# wrist_watch_v1.net
KiCad netlist of a schematic drawn in EAGLE
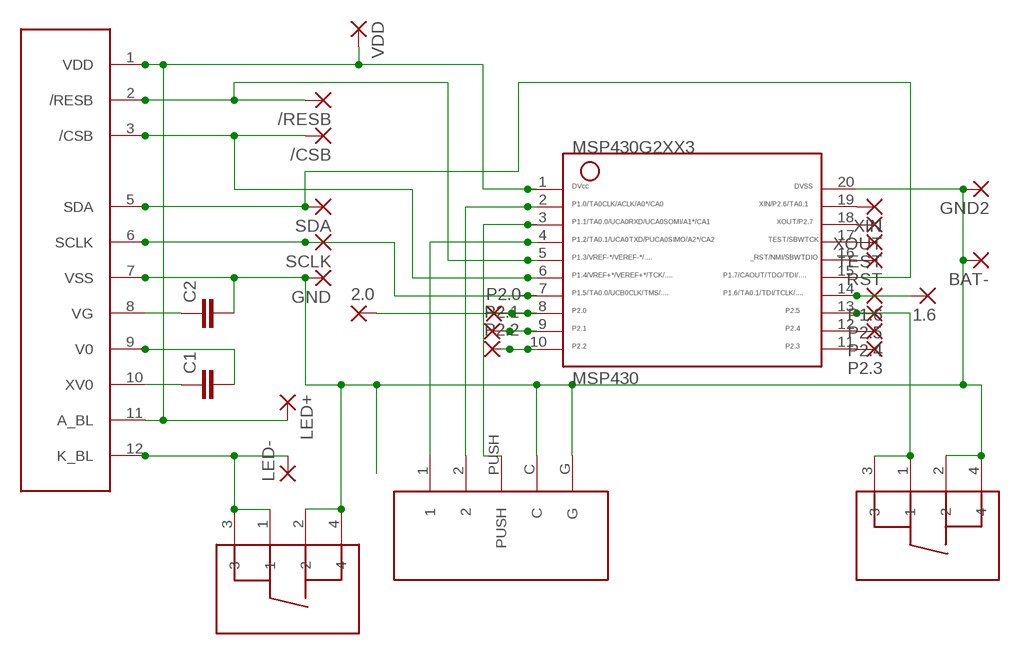
[diagram p0: schematic, sheet 1]

(export (version "E")
  (design (tool "Eeschema 10.0.6"))
  (components
    (comp (ref "/CSB")
      (value "1,6/0,9")
      (footprint "eagle-import:1,6_0,9")
      (libsource (lib "eagle-import") (part "1,6/0,9"))
    )
    (comp (ref "/RESB")
      (value "1,6/0,9")
      (footprint "eagle-import:1,6_0,9")
      (libsource (lib "eagle-import") (part "1,6/0,9"))
    )
    (comp (ref "1.6")
      (value "1,6/0,9")
      (footprint "eagle-import:1,6_0,9")
      (libsource (lib "eagle-import") (part "1,6/0,9"))
    )
    (comp (ref "2.0")
      (value "1,6/0,9")
      (footprint "eagle-import:1,6_0,9")
      (libsource (lib "eagle-import") (part "1,6/0,9"))
    )
    (comp (ref "BAT-")
      (value "SMD5")
      (footprint "eagle-import:SMD2,54-5,08")
      (libsource (lib "eagle-import") (part "SMD5"))
    )
    (comp (ref "C1")
      (value "CAP0805")
      (footprint "eagle-import:0805")
      (libsource (lib "eagle-import") (part "CAP0805"))
    )
    (comp (ref "C2")
      (value "CAP0805")
      (footprint "eagle-import:0805")
      (libsource (lib "eagle-import") (part "CAP0805"))
    )
    (comp (ref "GND")
      (value "1,6/0,9")
      (footprint "eagle-import:1,6_0,9")
      (libsource (lib "eagle-import") (part "1,6/0,9"))
    )
    (comp (ref "GND2")
      (value "SMD2")
      (footprint "eagle-import:SMD1,27-2,54")
      (libsource (lib "eagle-import") (part "SMD2"))
    )
    (comp (ref "LED+")
      (value "1,6/0,9")
      (footprint "eagle-import:1,6_0,9")
      (libsource (lib "eagle-import") (part "1,6/0,9"))
    )
    (comp (ref "LED-")
      (value "1,6/0,9")
      (footprint "eagle-import:1,6_0,9")
      (libsource (lib "eagle-import") (part "1,6/0,9"))
    )
    (comp (ref "MSP430")
      (value "G2XX3---PW20")
      (footprint "eagle-import:PW20")
      (libsource (lib "eagle-import") (part "G2XX3---PW20"))
    )
    (comp (ref "P1.6")
      (value "SMD2")
      (footprint "eagle-import:SMD1,27-2,54")
      (libsource (lib "eagle-import") (part "SMD2"))
    )
    (comp (ref "P2.0")
      (value "SMD2")
      (footprint "eagle-import:SMD1,27-2,54")
      (libsource (lib "eagle-import") (part "SMD2"))
    )
    (comp (ref "P2.1")
      (value "SMD2")
      (footprint "eagle-import:SMD1,27-2,54")
      (libsource (lib "eagle-import") (part "SMD2"))
    )
    (comp (ref "P2.2")
      (value "SMD2")
      (footprint "eagle-import:SMD1,27-2,54")
      (libsource (lib "eagle-import") (part "SMD2"))
    )
    (comp (ref "P2.3")
      (value "SMD2")
      (footprint "eagle-import:SMD1,27-2,54")
      (libsource (lib "eagle-import") (part "SMD2"))
    )
    (comp (ref "P2.4")
      (value "SMD2")
      (footprint "eagle-import:SMD1,27-2,54")
      (libsource (lib "eagle-import") (part "SMD2"))
    )
    (comp (ref "P2.5")
      (value "SMD2")
      (footprint "eagle-import:SMD1,27-2,54")
      (libsource (lib "eagle-import") (part "SMD2"))
    )
    (comp (ref "RST")
      (value "1,6/0,9")
      (footprint "eagle-import:1,6_0,9")
      (libsource (lib "eagle-import") (part "1,6/0,9"))
    )
    (comp (ref "SCLK")
      (value "1,6/0,9")
      (footprint "eagle-import:1,6_0,9")
      (libsource (lib "eagle-import") (part "1,6/0,9"))
    )
    (comp (ref "SDA")
      (value "1,6/0,9")
      (footprint "eagle-import:1,6_0,9")
      (libsource (lib "eagle-import") (part "1,6/0,9"))
    )
    (comp (ref "TEST")
      (value "1,6/0,9")
      (footprint "eagle-import:1,6_0,9")
      (libsource (lib "eagle-import") (part "1,6/0,9"))
    )
    (comp (ref "U$1")
      (value "PE9665WRFPE9665WRF-WHOLE")
      (footprint "eagle-import:PE9665WRF")
      (libsource (lib "eagle-import") (part "PE9665WRFPE9665WRF-WHOLE"))
    )
    (comp (ref "U$2")
      (value "MCPTCF-V")
      (footprint "eagle-import:MCPTCF-V")
      (libsource (lib "eagle-import") (part "MCPTCF-V"))
    )
    (comp (ref "U$3")
      (value "MCPL3-BC-V")
      (footprint "eagle-import:MCPL3-BC-V")
      (libsource (lib "eagle-import") (part "MCPL3-BC-V"))
    )
    (comp (ref "U$4")
      (value "MCPTCF-V")
      (footprint "eagle-import:MCPTCF-V")
      (libsource (lib "eagle-import") (part "MCPTCF-V"))
    )
    (comp (ref "VDD")
      (value "1,6/0,9")
      (footprint "eagle-import:1,6_0,9")
      (libsource (lib "eagle-import") (part "1,6/0,9"))
    )
    (comp (ref "XIN")
      (value "SMD2")
      (footprint "eagle-import:SMD1,27-2,54")
      (libsource (lib "eagle-import") (part "SMD2"))
    )
    (comp (ref "XOUT")
      (value "SMD2")
      (footprint "eagle-import:SMD1,27-2,54")
      (libsource (lib "eagle-import") (part "SMD2"))
    )
  )
  (nets
    (net (code "1") (name "Net-(/CSB-P)") (class "Default")
      (node (ref "/CSB") (pin "1") (pinfunction "P_1") (pintype "passive"))
      (node (ref "MSP430") (pin "6") (pinfunction "6_6") (pintype "bidirectional"))
      (node (ref "U$1") (pin "3") (pinfunction "/CSB_3") (pintype "bidirectional"))
    )
    (net (code "2") (name "Net-(/RESB-P)") (class "Default")
      (node (ref "/RESB") (pin "1") (pinfunction "P_1") (pintype "passive"))
      (node (ref "MSP430") (pin "5") (pinfunction "5_5") (pintype "bidirectional"))
      (node (ref "U$1") (pin "2") (pinfunction "/RESB_2") (pintype "bidirectional"))
    )
    (net (code "3") (name "Net-(1.6-P)") (class "Default")
      (node (ref "1.6") (pin "1") (pinfunction "P_1") (pintype "passive"))
      (node (ref "MSP430") (pin "14") (pinfunction "14_14") (pintype "bidirectional"))
      (node (ref "P1.6") (pin "1") (pinfunction "P_1") (pintype "passive"))
    )
    (net (code "4") (name "Net-(2.0-P)") (class "Default")
      (node (ref "2.0") (pin "1") (pinfunction "P_1") (pintype "passive"))
      (node (ref "MSP430") (pin "8") (pinfunction "8_8") (pintype "bidirectional"))
      (node (ref "P2.0") (pin "1") (pinfunction "P_1") (pintype "passive"))
    )
    (net (code "5") (name "Net-(BAT--P)") (class "Default")
      (node (ref "BAT-") (pin "1") (pinfunction "P_1") (pintype "passive"))
      (node (ref "C2") (pin "2") (pinfunction "2_2") (pintype "passive"))
      (node (ref "GND") (pin "1") (pinfunction "P_1") (pintype "passive"))
      (node (ref "GND2") (pin "1") (pinfunction "P_1") (pintype "passive"))
      (node (ref "MSP430") (pin "20") (pinfunction "20_20") (pintype "bidirectional"))
      (node (ref "U$1") (pin "7") (pinfunction "VSS_7") (pintype "bidirectional"))
      (node (ref "U$2") (pin "2") (pinfunction "2_2") (pintype "bidirectional"))
      (node (ref "U$2") (pin "4") (pinfunction "4_4") (pintype "bidirectional"))
      (node (ref "U$3") (pin "C") (pinfunction "C_C") (pintype "bidirectional"))
      (node (ref "U$3") (pin "G") (pinfunction "G_G") (pintype "bidirectional"))
      (node (ref "U$4") (pin "2") (pinfunction "2_2") (pintype "bidirectional"))
      (node (ref "U$4") (pin "4") (pinfunction "4_4") (pintype "bidirectional"))
    )
    (net (code "6") (name "Net-(LED+-P)") (class "Default")
      (node (ref "LED+") (pin "1") (pinfunction "P_1") (pintype "passive"))
      (node (ref "MSP430") (pin "1") (pinfunction "1_1") (pintype "bidirectional"))
      (node (ref "U$1") (pin "1") (pinfunction "VDD_1") (pintype "bidirectional"))
      (node (ref "U$1") (pin "11") (pinfunction "A_BL_11") (pintype "bidirectional"))
      (node (ref "VDD") (pin "1") (pinfunction "P_1") (pintype "passive"))
    )
    (net (code "7") (name "Net-(LED--P)") (class "Default")
      (node (ref "LED-") (pin "1") (pinfunction "P_1") (pintype "passive"))
      (node (ref "U$1") (pin "12") (pinfunction "K_BL_12") (pintype "bidirectional"))
      (node (ref "U$2") (pin "1") (pinfunction "1_1") (pintype "bidirectional"))
      (node (ref "U$2") (pin "3") (pinfunction "3_3") (pintype "bidirectional"))
    )
    (net (code "8") (name "Net-(MSP430-Pad2)") (class "Default")
      (node (ref "MSP430") (pin "2") (pinfunction "2_2") (pintype "bidirectional"))
      (node (ref "U$3") (pin "2") (pinfunction "2_2") (pintype "bidirectional"))
    )
    (net (code "9") (name "Net-(MSP430-Pad3)") (class "Default")
      (node (ref "MSP430") (pin "3") (pinfunction "3_3") (pintype "bidirectional"))
      (node (ref "U$3") (pin "PUSH") (pinfunction "PUSH_PUSH") (pintype "bidirectional"))
    )
    (net (code "10") (name "Net-(MSP430-Pad4)") (class "Default")
      (node (ref "MSP430") (pin "4") (pinfunction "4_4") (pintype "bidirectional"))
      (node (ref "U$3") (pin "1") (pinfunction "1_1") (pintype "bidirectional"))
    )
    (net (code "11") (name "Net-(P2.1-P)") (class "Default")
      (node (ref "MSP430") (pin "9") (pinfunction "9_9") (pintype "bidirectional"))
      (node (ref "P2.1") (pin "1") (pinfunction "P_1") (pintype "passive"))
    )
    (net (code "12") (name "Net-(P2.2-P)") (class "Default")
      (node (ref "MSP430") (pin "10") (pinfunction "10_10") (pintype "bidirectional"))
      (node (ref "P2.2") (pin "1") (pinfunction "P_1") (pintype "passive"))
    )
    (net (code "13") (name "Net-(P2.3-P)") (class "Default")
      (node (ref "MSP430") (pin "11") (pinfunction "11_11") (pintype "bidirectional"))
      (node (ref "P2.3") (pin "1") (pinfunction "P_1") (pintype "passive"))
    )
    (net (code "14") (name "Net-(P2.4-P)") (class "Default")
      (node (ref "MSP430") (pin "12") (pinfunction "12_12") (pintype "bidirectional"))
      (node (ref "P2.4") (pin "1") (pinfunction "P_1") (pintype "passive"))
    )
    (net (code "15") (name "Net-(P2.5-P)") (class "Default")
      (node (ref "MSP430") (pin "13") (pinfunction "13_13") (pintype "bidirectional"))
      (node (ref "P2.5") (pin "1") (pinfunction "P_1") (pintype "passive"))
      (node (ref "U$4") (pin "1") (pinfunction "1_1") (pintype "bidirectional"))
      (node (ref "U$4") (pin "3") (pinfunction "3_3") (pintype "bidirectional"))
    )
    (net (code "16") (name "Net-(RST-P)") (class "Default")
      (node (ref "MSP430") (pin "16") (pinfunction "16_16") (pintype "bidirectional"))
      (node (ref "RST") (pin "1") (pinfunction "P_1") (pintype "passive"))
    )
    (net (code "17") (name "Net-(SCLK-P)") (class "Default")
      (node (ref "MSP430") (pin "7") (pinfunction "7_7") (pintype "bidirectional"))
      (node (ref "SCLK") (pin "1") (pinfunction "P_1") (pintype "passive"))
      (node (ref "U$1") (pin "6") (pinfunction "SCLK_6") (pintype "bidirectional"))
    )
    (net (code "18") (name "Net-(SDA-P)") (class "Default")
      (node (ref "MSP430") (pin "15") (pinfunction "15_15") (pintype "bidirectional"))
      (node (ref "SDA") (pin "1") (pinfunction "P_1") (pintype "passive"))
      (node (ref "U$1") (pin "5") (pinfunction "SDA_5") (pintype "bidirectional"))
    )
    (net (code "19") (name "Net-(TEST-P)") (class "Default")
      (node (ref "MSP430") (pin "17") (pinfunction "17_17") (pintype "bidirectional"))
      (node (ref "TEST") (pin "1") (pinfunction "P_1") (pintype "passive"))
    )
    (net (code "20") (name "Net-(U$1-V0)") (class "Default")
      (node (ref "C1") (pin "2") (pinfunction "2_2") (pintype "passive"))
      (node (ref "U$1") (pin "9") (pinfunction "V0_9") (pintype "bidirectional"))
    )
    (net (code "21") (name "Net-(U$1-VG)") (class "Default")
      (node (ref "C2") (pin "1") (pinfunction "1_1") (pintype "passive"))
      (node (ref "U$1") (pin "8") (pinfunction "VG_8") (pintype "bidirectional"))
    )
    (net (code "22") (name "Net-(U$1-XV0)") (class "Default")
      (node (ref "C1") (pin "1") (pinfunction "1_1") (pintype "passive"))
      (node (ref "U$1") (pin "10") (pinfunction "XV0_10") (pintype "bidirectional"))
    )
    (net (code "23") (name "Net-(XIN-P)") (class "Default")
      (node (ref "MSP430") (pin "19") (pinfunction "19_19") (pintype "bidirectional"))
      (node (ref "XIN") (pin "1") (pinfunction "P_1") (pintype "passive"))
    )
    (net (code "24") (name "Net-(XOUT-P)") (class "Default")
      (node (ref "MSP430") (pin "18") (pinfunction "18_18") (pintype "bidirectional"))
      (node (ref "XOUT") (pin "1") (pinfunction "P_1") (pintype "passive"))
    )
  )
)
